# blackmagic_richardeoin.net
KiCad netlist of a schematic drawn in EAGLE
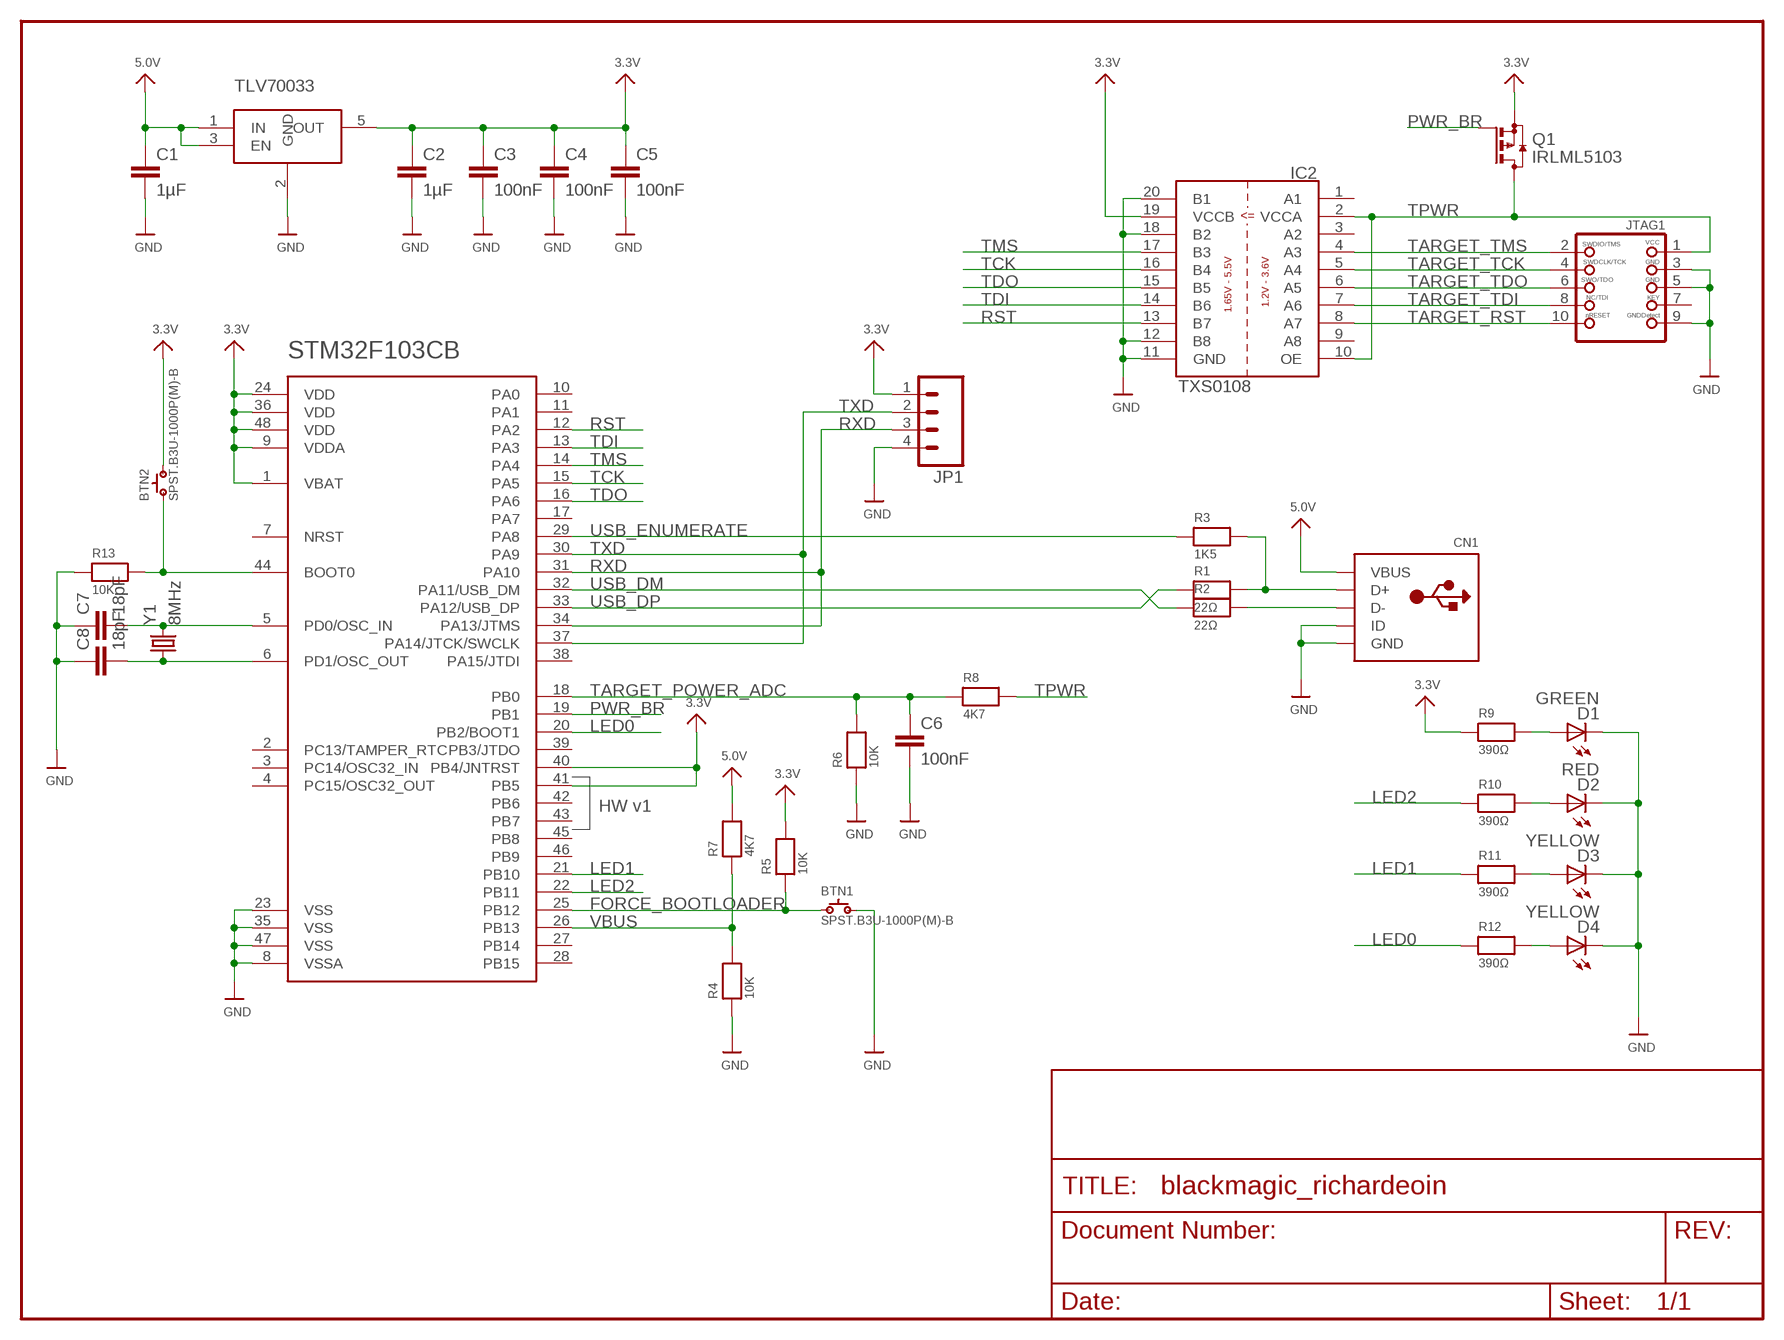
[diagram p0: schematic, sheet 1]

(export (version "E")
  (design (tool "Eeschema 10.0.6"))
  (components
    (comp (ref "BTN1")
      (value "SPST.B3U-1000P(M)-B")
      (footprint "eagle-import:B3U-1000P(M)-B")
      (libsource (lib "eagle-import") (part "SPST.B3U-1000P(M)-B"))
    )
    (comp (ref "BTN2")
      (value "SPST.B3U-1000P(M)-B")
      (footprint "eagle-import:B3U-1000P(M)-B")
      (libsource (lib "eagle-import") (part "SPST.B3U-1000P(M)-B"))
    )
    (comp (ref "C1")
      (value "1µF")
      (footprint "eagle-import:C0603K")
      (libsource (lib "eagle-import") (part "C-EUC0603K"))
    )
    (comp (ref "C2")
      (value "1µF")
      (footprint "eagle-import:C0603K")
      (libsource (lib "eagle-import") (part "C-EUC0603K"))
    )
    (comp (ref "C3")
      (value "100nF")
      (footprint "eagle-import:C0603K")
      (libsource (lib "eagle-import") (part "C-EUC0603K"))
    )
    (comp (ref "C4")
      (value "100nF")
      (footprint "eagle-import:C0603K")
      (libsource (lib "eagle-import") (part "C-EUC0603K"))
    )
    (comp (ref "C5")
      (value "100nF")
      (footprint "eagle-import:C0603K")
      (libsource (lib "eagle-import") (part "C-EUC0603K"))
    )
    (comp (ref "C6")
      (value "100nF")
      (footprint "eagle-import:C0603K")
      (libsource (lib "eagle-import") (part "C-EUC0603K"))
    )
    (comp (ref "C7")
      (value "18pF")
      (footprint "eagle-import:C0603K")
      (libsource (lib "eagle-import") (part "C-EUC0603K"))
    )
    (comp (ref "C8")
      (value "18pF")
      (footprint "eagle-import:C0603K")
      (libsource (lib "eagle-import") (part "C-EUC0603K"))
    )
    (comp (ref "CN1")
      (value "USBMINIB")
      (footprint "eagle-import:USB-MINIB")
      (libsource (lib "eagle-import") (part "USBMINIB"))
    )
    (comp (ref "D1")
      (value "GREEN")
      (footprint "eagle-import:CHIPLED_0603")
      (libsource (lib "eagle-import") (part "LEDCHIPLED_0603"))
    )
    (comp (ref "D2")
      (value "RED")
      (footprint "eagle-import:CHIPLED_0603")
      (libsource (lib "eagle-import") (part "LEDCHIPLED_0603"))
    )
    (comp (ref "D3")
      (value "YELLOW")
      (footprint "eagle-import:CHIPLED_0603")
      (libsource (lib "eagle-import") (part "LEDCHIPLED_0603"))
    )
    (comp (ref "D4")
      (value "YELLOW")
      (footprint "eagle-import:CHIPLED_0603")
      (libsource (lib "eagle-import") (part "LEDCHIPLED_0603"))
    )
    (comp (ref "IC1")
      (value "STM32F_48PIN")
      (footprint "eagle-import:TQFP48")
      (libsource (lib "eagle-import") (part "STM32F_48PIN"))
    )
    (comp (ref "IC2")
      (value "TXS0108")
      (footprint "eagle-import:TSSOP20")
      (libsource (lib "eagle-import") (part "TX0108PWR"))
    )
    (comp (ref "IC3")
      (value "TLV70033DCK")
      (footprint "eagle-import:SC70-5L")
      (libsource (lib "eagle-import") (part "TLV700DCK"))
    )
    (comp (ref "JP1")
      (value "M04LOCK")
      (footprint "eagle-import:1X04_LOCK")
      (libsource (lib "eagle-import") (part "M04LOCK"))
    )
    (comp (ref "JTAG1")
      (value "JTAG-CORTEXM3")
      (footprint "eagle-import:2X05_1.27MM_SMT")
      (libsource (lib "eagle-import") (part "JTAG-CORTEXM3"))
    )
    (comp (ref "Q1")
      (value "IRLML5103")
      (footprint "eagle-import:SOT23")
      (libsource (lib "eagle-import") (part "BSS84"))
    )
    (comp (ref "R1")
      (value "22Ω")
      (footprint "eagle-import:0603-MINI")
      (libsource (lib "eagle-import") (part "RESISTOR0603MINI"))
    )
    (comp (ref "R2")
      (value "22Ω")
      (footprint "eagle-import:0603-MINI")
      (libsource (lib "eagle-import") (part "RESISTOR0603MINI"))
    )
    (comp (ref "R3")
      (value "1K5")
      (footprint "eagle-import:0603-MINI")
      (libsource (lib "eagle-import") (part "RESISTOR0603MINI"))
    )
    (comp (ref "R4")
      (value "10K")
      (footprint "eagle-import:0603-MINI")
      (libsource (lib "eagle-import") (part "RESISTOR0603MINI"))
    )
    (comp (ref "R5")
      (value "10K")
      (footprint "eagle-import:0603-MINI")
      (libsource (lib "eagle-import") (part "RESISTOR0603MINI"))
    )
    (comp (ref "R6")
      (value "10K")
      (footprint "eagle-import:0603-MINI")
      (libsource (lib "eagle-import") (part "RESISTOR0603MINI"))
    )
    (comp (ref "R7")
      (value "4K7")
      (footprint "eagle-import:0603-MINI")
      (libsource (lib "eagle-import") (part "RESISTOR0603MINI"))
    )
    (comp (ref "R8")
      (value "4K7")
      (footprint "eagle-import:0603-MINI")
      (libsource (lib "eagle-import") (part "RESISTOR0603MINI"))
    )
    (comp (ref "R9")
      (value "390Ω")
      (footprint "eagle-import:0603-MINI")
      (libsource (lib "eagle-import") (part "RESISTOR0603MINI"))
    )
    (comp (ref "R10")
      (value "390Ω")
      (footprint "eagle-import:0603-MINI")
      (libsource (lib "eagle-import") (part "RESISTOR0603MINI"))
    )
    (comp (ref "R11")
      (value "390Ω")
      (footprint "eagle-import:0603-MINI")
      (libsource (lib "eagle-import") (part "RESISTOR0603MINI"))
    )
    (comp (ref "R12")
      (value "390Ω")
      (footprint "eagle-import:0603-MINI")
      (libsource (lib "eagle-import") (part "RESISTOR0603MINI"))
    )
    (comp (ref "R13")
      (value "10K")
      (footprint "eagle-import:0603-MINI")
      (libsource (lib "eagle-import") (part "RESISTOR0603MINI"))
    )
    (comp (ref "Y1")
      (value "8MHz")
      (footprint "eagle-import:CRYSTAL-SMD-5X3")
      (libsource (lib "eagle-import") (part "CRYSTAL5X3"))
    )
  )
  (nets
    (net (code "1") (name "/FORCE_BOOTLOADER") (class "Default")
      (node (ref "BTN1") (pin "1") (pinfunction "1_1") (pintype "bidirectional"))
      (node (ref "IC1") (pin "25") (pinfunction "PB12_25") (pintype "bidirectional"))
      (node (ref "R5") (pin "1") (pinfunction "1_1") (pintype "passive"))
    )
    (net (code "2") (name "/LED0") (class "Default")
      (node (ref "IC1") (pin "20") (pinfunction "PB2/BOOT1_20") (pintype "bidirectional"))
      (node (ref "R12") (pin "1") (pinfunction "1_1") (pintype "passive"))
    )
    (net (code "3") (name "/LED1") (class "Default")
      (node (ref "IC1") (pin "21") (pinfunction "PB10_21") (pintype "bidirectional"))
      (node (ref "R11") (pin "1") (pinfunction "1_1") (pintype "passive"))
    )
    (net (code "4") (name "/LED2") (class "Default")
      (node (ref "IC1") (pin "22") (pinfunction "PB11_22") (pintype "bidirectional"))
      (node (ref "R10") (pin "1") (pinfunction "1_1") (pintype "passive"))
    )
    (net (code "5") (name "/PWR_BR") (class "Default")
      (node (ref "IC1") (pin "19") (pinfunction "PB1_19") (pintype "bidirectional"))
      (node (ref "Q1") (pin "1") (pinfunction "G_1") (pintype "passive"))
    )
    (net (code "6") (name "/RST") (class "Default")
      (node (ref "IC1") (pin "12") (pinfunction "PA2_12") (pintype "bidirectional"))
      (node (ref "IC2") (pin "13") (pinfunction "B7_13") (pintype "bidirectional"))
    )
    (net (code "7") (name "/RXD") (class "Default")
      (node (ref "IC1") (pin "31") (pinfunction "PA10_31") (pintype "bidirectional"))
      (node (ref "IC1") (pin "34") (pinfunction "PA13/JTMS_34") (pintype "bidirectional"))
      (node (ref "JP1") (pin "3") (pinfunction "3_3") (pintype "passive"))
    )
    (net (code "8") (name "/TARGET_POWER_ADC") (class "Default")
      (node (ref "C6") (pin "1") (pinfunction "1_1") (pintype "passive"))
      (node (ref "IC1") (pin "18") (pinfunction "PB0_18") (pintype "bidirectional"))
      (node (ref "R6") (pin "2") (pinfunction "2_2") (pintype "passive"))
      (node (ref "R8") (pin "1") (pinfunction "1_1") (pintype "passive"))
    )
    (net (code "9") (name "/TARGET_RST") (class "Default")
      (node (ref "IC2") (pin "8") (pinfunction "A7_8") (pintype "bidirectional"))
      (node (ref "JTAG1") (pin "10") (pinfunction "10_10") (pintype "passive"))
    )
    (net (code "10") (name "/TARGET_TCK") (class "Default")
      (node (ref "IC2") (pin "5") (pinfunction "A4_5") (pintype "bidirectional"))
      (node (ref "JTAG1") (pin "4") (pinfunction "4_4") (pintype "passive"))
    )
    (net (code "11") (name "/TARGET_TDI") (class "Default")
      (node (ref "IC2") (pin "7") (pinfunction "A6_7") (pintype "bidirectional"))
      (node (ref "JTAG1") (pin "8") (pinfunction "8_8") (pintype "passive"))
    )
    (net (code "12") (name "/TARGET_TDO") (class "Default")
      (node (ref "IC2") (pin "6") (pinfunction "A5_6") (pintype "bidirectional"))
      (node (ref "JTAG1") (pin "6") (pinfunction "6_6") (pintype "passive"))
    )
    (net (code "13") (name "/TARGET_TMS") (class "Default")
      (node (ref "IC2") (pin "4") (pinfunction "A3_4") (pintype "bidirectional"))
      (node (ref "JTAG1") (pin "2") (pinfunction "2_2") (pintype "passive"))
    )
    (net (code "14") (name "/TCK") (class "Default")
      (node (ref "IC1") (pin "15") (pinfunction "PA5_15") (pintype "bidirectional"))
      (node (ref "IC2") (pin "16") (pinfunction "B4_16") (pintype "bidirectional"))
    )
    (net (code "15") (name "/TDI") (class "Default")
      (node (ref "IC1") (pin "13") (pinfunction "PA3_13") (pintype "bidirectional"))
      (node (ref "IC2") (pin "14") (pinfunction "B6_14") (pintype "bidirectional"))
    )
    (net (code "16") (name "/TDO") (class "Default")
      (node (ref "IC1") (pin "16") (pinfunction "PA6_16") (pintype "bidirectional"))
      (node (ref "IC2") (pin "15") (pinfunction "B5_15") (pintype "bidirectional"))
    )
    (net (code "17") (name "/TMS") (class "Default")
      (node (ref "IC1") (pin "14") (pinfunction "PA4_14") (pintype "bidirectional"))
      (node (ref "IC2") (pin "17") (pinfunction "B3_17") (pintype "bidirectional"))
    )
    (net (code "18") (name "/TPWR") (class "Default")
      (node (ref "IC2") (pin "10") (pinfunction "OE_10") (pintype "input"))
      (node (ref "IC2") (pin "2") (pinfunction "VCCA_2") (pintype "passive"))
      (node (ref "JTAG1") (pin "1") (pinfunction "1_1") (pintype "passive"))
      (node (ref "Q1") (pin "3") (pinfunction "D_3") (pintype "passive"))
      (node (ref "R8") (pin "2") (pinfunction "2_2") (pintype "passive"))
    )
    (net (code "19") (name "/TXD") (class "Default")
      (node (ref "IC1") (pin "30") (pinfunction "PA9_30") (pintype "bidirectional"))
      (node (ref "IC1") (pin "37") (pinfunction "PA14/JTCK/SWCLK_37") (pintype "bidirectional"))
      (node (ref "JP1") (pin "2") (pinfunction "2_2") (pintype "passive"))
    )
    (net (code "20") (name "/USB_DM") (class "Default")
      (node (ref "IC1") (pin "32") (pinfunction "PA11/USB_DM_32") (pintype "bidirectional"))
      (node (ref "R2") (pin "1") (pinfunction "1_1") (pintype "passive"))
    )
    (net (code "21") (name "/USB_DP") (class "Default")
      (node (ref "IC1") (pin "33") (pinfunction "PA12/USB_DP_33") (pintype "bidirectional"))
      (node (ref "R1") (pin "1") (pinfunction "1_1") (pintype "passive"))
    )
    (net (code "22") (name "/USB_ENUMERATE") (class "Default")
      (node (ref "IC1") (pin "29") (pinfunction "PA8_29") (pintype "bidirectional"))
      (node (ref "R3") (pin "1") (pinfunction "1_1") (pintype "passive"))
    )
    (net (code "23") (name "/VBUS") (class "Default")
      (node (ref "IC1") (pin "26") (pinfunction "PB13_26") (pintype "bidirectional"))
      (node (ref "R4") (pin "2") (pinfunction "2_2") (pintype "passive"))
      (node (ref "R7") (pin "1") (pinfunction "1_1") (pintype "passive"))
    )
    (net (code "24") (name "3.3V") (class "Default")
      (node (ref "BTN2") (pin "2") (pinfunction "2_2") (pintype "bidirectional"))
      (node (ref "C2") (pin "1") (pinfunction "1_1") (pintype "passive"))
      (node (ref "C3") (pin "1") (pinfunction "1_1") (pintype "passive"))
      (node (ref "C4") (pin "1") (pinfunction "1_1") (pintype "passive"))
      (node (ref "C5") (pin "1") (pinfunction "1_1") (pintype "passive"))
      (node (ref "IC1") (pin "1") (pinfunction "VBAT_1") (pintype "bidirectional"))
      (node (ref "IC1") (pin "24") (pinfunction "VDD_24") (pintype "bidirectional"))
      (node (ref "IC1") (pin "36") (pinfunction "VDD_36") (pintype "bidirectional"))
      (node (ref "IC1") (pin "40") (pinfunction "PB4/JNTRST_40") (pintype "bidirectional"))
      (node (ref "IC1") (pin "41") (pinfunction "PB5_41") (pintype "bidirectional"))
      (node (ref "IC1") (pin "48") (pinfunction "VDD_48") (pintype "bidirectional"))
      (node (ref "IC1") (pin "9") (pinfunction "VDDA_9") (pintype "bidirectional"))
      (node (ref "IC2") (pin "19") (pinfunction "VCCB_19") (pintype "passive"))
      (node (ref "IC3") (pin "5") (pinfunction "OUT_5") (pintype "bidirectional"))
      (node (ref "JP1") (pin "1") (pinfunction "1_1") (pintype "passive"))
      (node (ref "Q1") (pin "2") (pinfunction "S_2") (pintype "passive"))
      (node (ref "R5") (pin "2") (pinfunction "2_2") (pintype "passive"))
      (node (ref "R9") (pin "1") (pinfunction "1_1") (pintype "passive"))
    )
    (net (code "25") (name "5.0V") (class "Default")
      (node (ref "C1") (pin "1") (pinfunction "1_1") (pintype "passive"))
      (node (ref "CN1") (pin "VBUS") (pinfunction "VBUS_VBUS") (pintype "power_in"))
      (node (ref "IC3") (pin "1") (pinfunction "IN_1") (pintype "bidirectional"))
      (node (ref "IC3") (pin "3") (pinfunction "EN_3") (pintype "bidirectional"))
      (node (ref "R7") (pin "2") (pinfunction "2_2") (pintype "passive"))
    )
    (net (code "26") (name "GND") (class "Default")
      (node (ref "BTN1") (pin "2") (pinfunction "2_2") (pintype "bidirectional"))
      (node (ref "C1") (pin "2") (pinfunction "2_2") (pintype "passive"))
      (node (ref "C2") (pin "2") (pinfunction "2_2") (pintype "passive"))
      (node (ref "C3") (pin "2") (pinfunction "2_2") (pintype "passive"))
      (node (ref "C4") (pin "2") (pinfunction "2_2") (pintype "passive"))
      (node (ref "C5") (pin "2") (pinfunction "2_2") (pintype "passive"))
      (node (ref "C6") (pin "2") (pinfunction "2_2") (pintype "passive"))
      (node (ref "C7") (pin "1") (pinfunction "1_1") (pintype "passive"))
      (node (ref "C8") (pin "1") (pinfunction "1_1") (pintype "passive"))
      (node (ref "CN1") (pin "GND") (pinfunction "GND_GND") (pintype "power_in"))
      (node (ref "CN1") (pin "ID") (pinfunction "ID_ID") (pintype "bidirectional"))
      (node (ref "D1") (pin "C") (pinfunction "C_C") (pintype "passive"))
      (node (ref "D2") (pin "C") (pinfunction "C_C") (pintype "passive"))
      (node (ref "D3") (pin "C") (pinfunction "C_C") (pintype "passive"))
      (node (ref "D4") (pin "C") (pinfunction "C_C") (pintype "passive"))
      (node (ref "IC1") (pin "23") (pinfunction "VSS_23") (pintype "bidirectional"))
      (node (ref "IC1") (pin "35") (pinfunction "VSS_35") (pintype "bidirectional"))
      (node (ref "IC1") (pin "47") (pinfunction "VSS_47") (pintype "bidirectional"))
      (node (ref "IC1") (pin "8") (pinfunction "VSSA_8") (pintype "bidirectional"))
      (node (ref "IC2") (pin "11") (pinfunction "GND_11") (pintype "passive"))
      (node (ref "IC2") (pin "12") (pinfunction "B8_12") (pintype "bidirectional"))
      (node (ref "IC2") (pin "18") (pinfunction "B2_18") (pintype "bidirectional"))
      (node (ref "IC2") (pin "20") (pinfunction "B1_20") (pintype "bidirectional"))
      (node (ref "IC3") (pin "2") (pinfunction "GND_2") (pintype "bidirectional"))
      (node (ref "JP1") (pin "4") (pinfunction "4_4") (pintype "passive"))
      (node (ref "JTAG1") (pin "3") (pinfunction "3_3") (pintype "passive"))
      (node (ref "JTAG1") (pin "5") (pinfunction "5_5") (pintype "passive"))
      (node (ref "JTAG1") (pin "9") (pinfunction "9_9") (pintype "passive"))
      (node (ref "R13") (pin "1") (pinfunction "1_1") (pintype "passive"))
      (node (ref "R4") (pin "1") (pinfunction "1_1") (pintype "passive"))
      (node (ref "R6") (pin "1") (pinfunction "1_1") (pintype "passive"))
    )
    (net (code "27") (name "Net-(CN1-PadD+)") (class "Default")
      (node (ref "CN1") (pin "D+") (pinfunction "D+_D+") (pintype "bidirectional"))
      (node (ref "R1") (pin "2") (pinfunction "2_2") (pintype "passive"))
      (node (ref "R3") (pin "2") (pinfunction "2_2") (pintype "passive"))
    )
    (net (code "28") (name "Net-(CN1-PadD-)") (class "Default")
      (node (ref "CN1") (pin "D-") (pinfunction "D-_D-") (pintype "bidirectional"))
      (node (ref "R2") (pin "2") (pinfunction "2_2") (pintype "passive"))
    )
    (net (code "29") (name "Net-(D1-PadA)") (class "Default")
      (node (ref "D1") (pin "A") (pinfunction "A_A") (pintype "passive"))
      (node (ref "R9") (pin "2") (pinfunction "2_2") (pintype "passive"))
    )
    (net (code "30") (name "Net-(D2-PadA)") (class "Default")
      (node (ref "D2") (pin "A") (pinfunction "A_A") (pintype "passive"))
      (node (ref "R10") (pin "2") (pinfunction "2_2") (pintype "passive"))
    )
    (net (code "31") (name "Net-(D3-PadA)") (class "Default")
      (node (ref "D3") (pin "A") (pinfunction "A_A") (pintype "passive"))
      (node (ref "R11") (pin "2") (pinfunction "2_2") (pintype "passive"))
    )
    (net (code "32") (name "Net-(D4-PadA)") (class "Default")
      (node (ref "D4") (pin "A") (pinfunction "A_A") (pintype "passive"))
      (node (ref "R12") (pin "2") (pinfunction "2_2") (pintype "passive"))
    )
    (net (code "33") (name "Net-(IC1-BOOT0)") (class "Default")
      (node (ref "BTN2") (pin "1") (pinfunction "1_1") (pintype "bidirectional"))
      (node (ref "IC1") (pin "44") (pinfunction "BOOT0_44") (pintype "bidirectional"))
      (node (ref "R13") (pin "2") (pinfunction "2_2") (pintype "passive"))
    )
    (net (code "34") (name "Net-(IC1-PD0{slash}OSC_IN)") (class "Default")
      (node (ref "C7") (pin "2") (pinfunction "2_2") (pintype "passive"))
      (node (ref "IC1") (pin "5") (pinfunction "PD0/OSC_IN_5") (pintype "bidirectional"))
      (node (ref "Y1") (pin "3") (pinfunction "2_3") (pintype "passive"))
    )
    (net (code "35") (name "Net-(IC1-PD1{slash}OSC_OUT)") (class "Default")
      (node (ref "C8") (pin "2") (pinfunction "2_2") (pintype "passive"))
      (node (ref "IC1") (pin "6") (pinfunction "PD1/OSC_OUT_6") (pintype "bidirectional"))
      (node (ref "Y1") (pin "1") (pinfunction "1_1") (pintype "passive"))
    )
    (net (code "36") (name "unconnected-(IC1-NRST-Pad7)") (class "Default")
      (node (ref "IC1") (pin "7") (pinfunction "NRST_7") (pintype "bidirectional"))
    )
    (net (code "37") (name "unconnected-(IC1-PA0-Pad10)") (class "Default")
      (node (ref "IC1") (pin "10") (pinfunction "PA0_10") (pintype "bidirectional"))
    )
    (net (code "38") (name "unconnected-(IC1-PA1-Pad11)") (class "Default")
      (node (ref "IC1") (pin "11") (pinfunction "PA1_11") (pintype "bidirectional"))
    )
    (net (code "39") (name "unconnected-(IC1-PA7-Pad17)") (class "Default")
      (node (ref "IC1") (pin "17") (pinfunction "PA7_17") (pintype "bidirectional"))
    )
    (net (code "40") (name "unconnected-(IC1-PA15{slash}JTDI-Pad38)") (class "Default")
      (node (ref "IC1") (pin "38") (pinfunction "PA15/JTDI_38") (pintype "bidirectional"))
    )
    (net (code "41") (name "unconnected-(IC1-PB3{slash}JTDO-Pad39)") (class "Default")
      (node (ref "IC1") (pin "39") (pinfunction "PB3/JTDO_39") (pintype "bidirectional"))
    )
    (net (code "42") (name "unconnected-(IC1-PB6-Pad42)") (class "Default")
      (node (ref "IC1") (pin "42") (pinfunction "PB6_42") (pintype "bidirectional"))
    )
    (net (code "43") (name "unconnected-(IC1-PB7-Pad43)") (class "Default")
      (node (ref "IC1") (pin "43") (pinfunction "PB7_43") (pintype "bidirectional"))
    )
    (net (code "44") (name "unconnected-(IC1-PB8-Pad45)") (class "Default")
      (node (ref "IC1") (pin "45") (pinfunction "PB8_45") (pintype "bidirectional"))
    )
    (net (code "45") (name "unconnected-(IC1-PB9-Pad46)") (class "Default")
      (node (ref "IC1") (pin "46") (pinfunction "PB9_46") (pintype "bidirectional"))
    )
    (net (code "46") (name "unconnected-(IC1-PB14-Pad27)") (class "Default")
      (node (ref "IC1") (pin "27") (pinfunction "PB14_27") (pintype "bidirectional"))
    )
    (net (code "47") (name "unconnected-(IC1-PB15-Pad28)") (class "Default")
      (node (ref "IC1") (pin "28") (pinfunction "PB15_28") (pintype "bidirectional"))
    )
    (net (code "48") (name "unconnected-(IC1-PC13{slash}TAMPER_RTC-Pad2)") (class "Default")
      (node (ref "IC1") (pin "2") (pinfunction "PC13/TAMPER_RTC_2") (pintype "bidirectional"))
    )
    (net (code "49") (name "unconnected-(IC1-PC14{slash}OSC32_IN-Pad3)") (class "Default")
      (node (ref "IC1") (pin "3") (pinfunction "PC14/OSC32_IN_3") (pintype "bidirectional"))
    )
    (net (code "50") (name "unconnected-(IC1-PC15{slash}OSC32_OUT-Pad4)") (class "Default")
      (node (ref "IC1") (pin "4") (pinfunction "PC15/OSC32_OUT_4") (pintype "bidirectional"))
    )
    (net (code "51") (name "unconnected-(IC2-A1-Pad1)") (class "Default")
      (node (ref "IC2") (pin "1") (pinfunction "A1_1") (pintype "bidirectional"))
    )
    (net (code "52") (name "unconnected-(IC2-A2-Pad3)") (class "Default")
      (node (ref "IC2") (pin "3") (pinfunction "A2_3") (pintype "bidirectional"))
    )
    (net (code "53") (name "unconnected-(IC2-A8-Pad9)") (class "Default")
      (node (ref "IC2") (pin "9") (pinfunction "A8_9") (pintype "bidirectional"))
    )
    (net (code "54") (name "unconnected-(JTAG1-Pad7)") (class "Default")
      (node (ref "JTAG1") (pin "7") (pinfunction "7_7") (pintype "passive"))
    )
  )
)
